# MKV58_1.net
KiCad netlist of a schematic drawn in Altium Designer
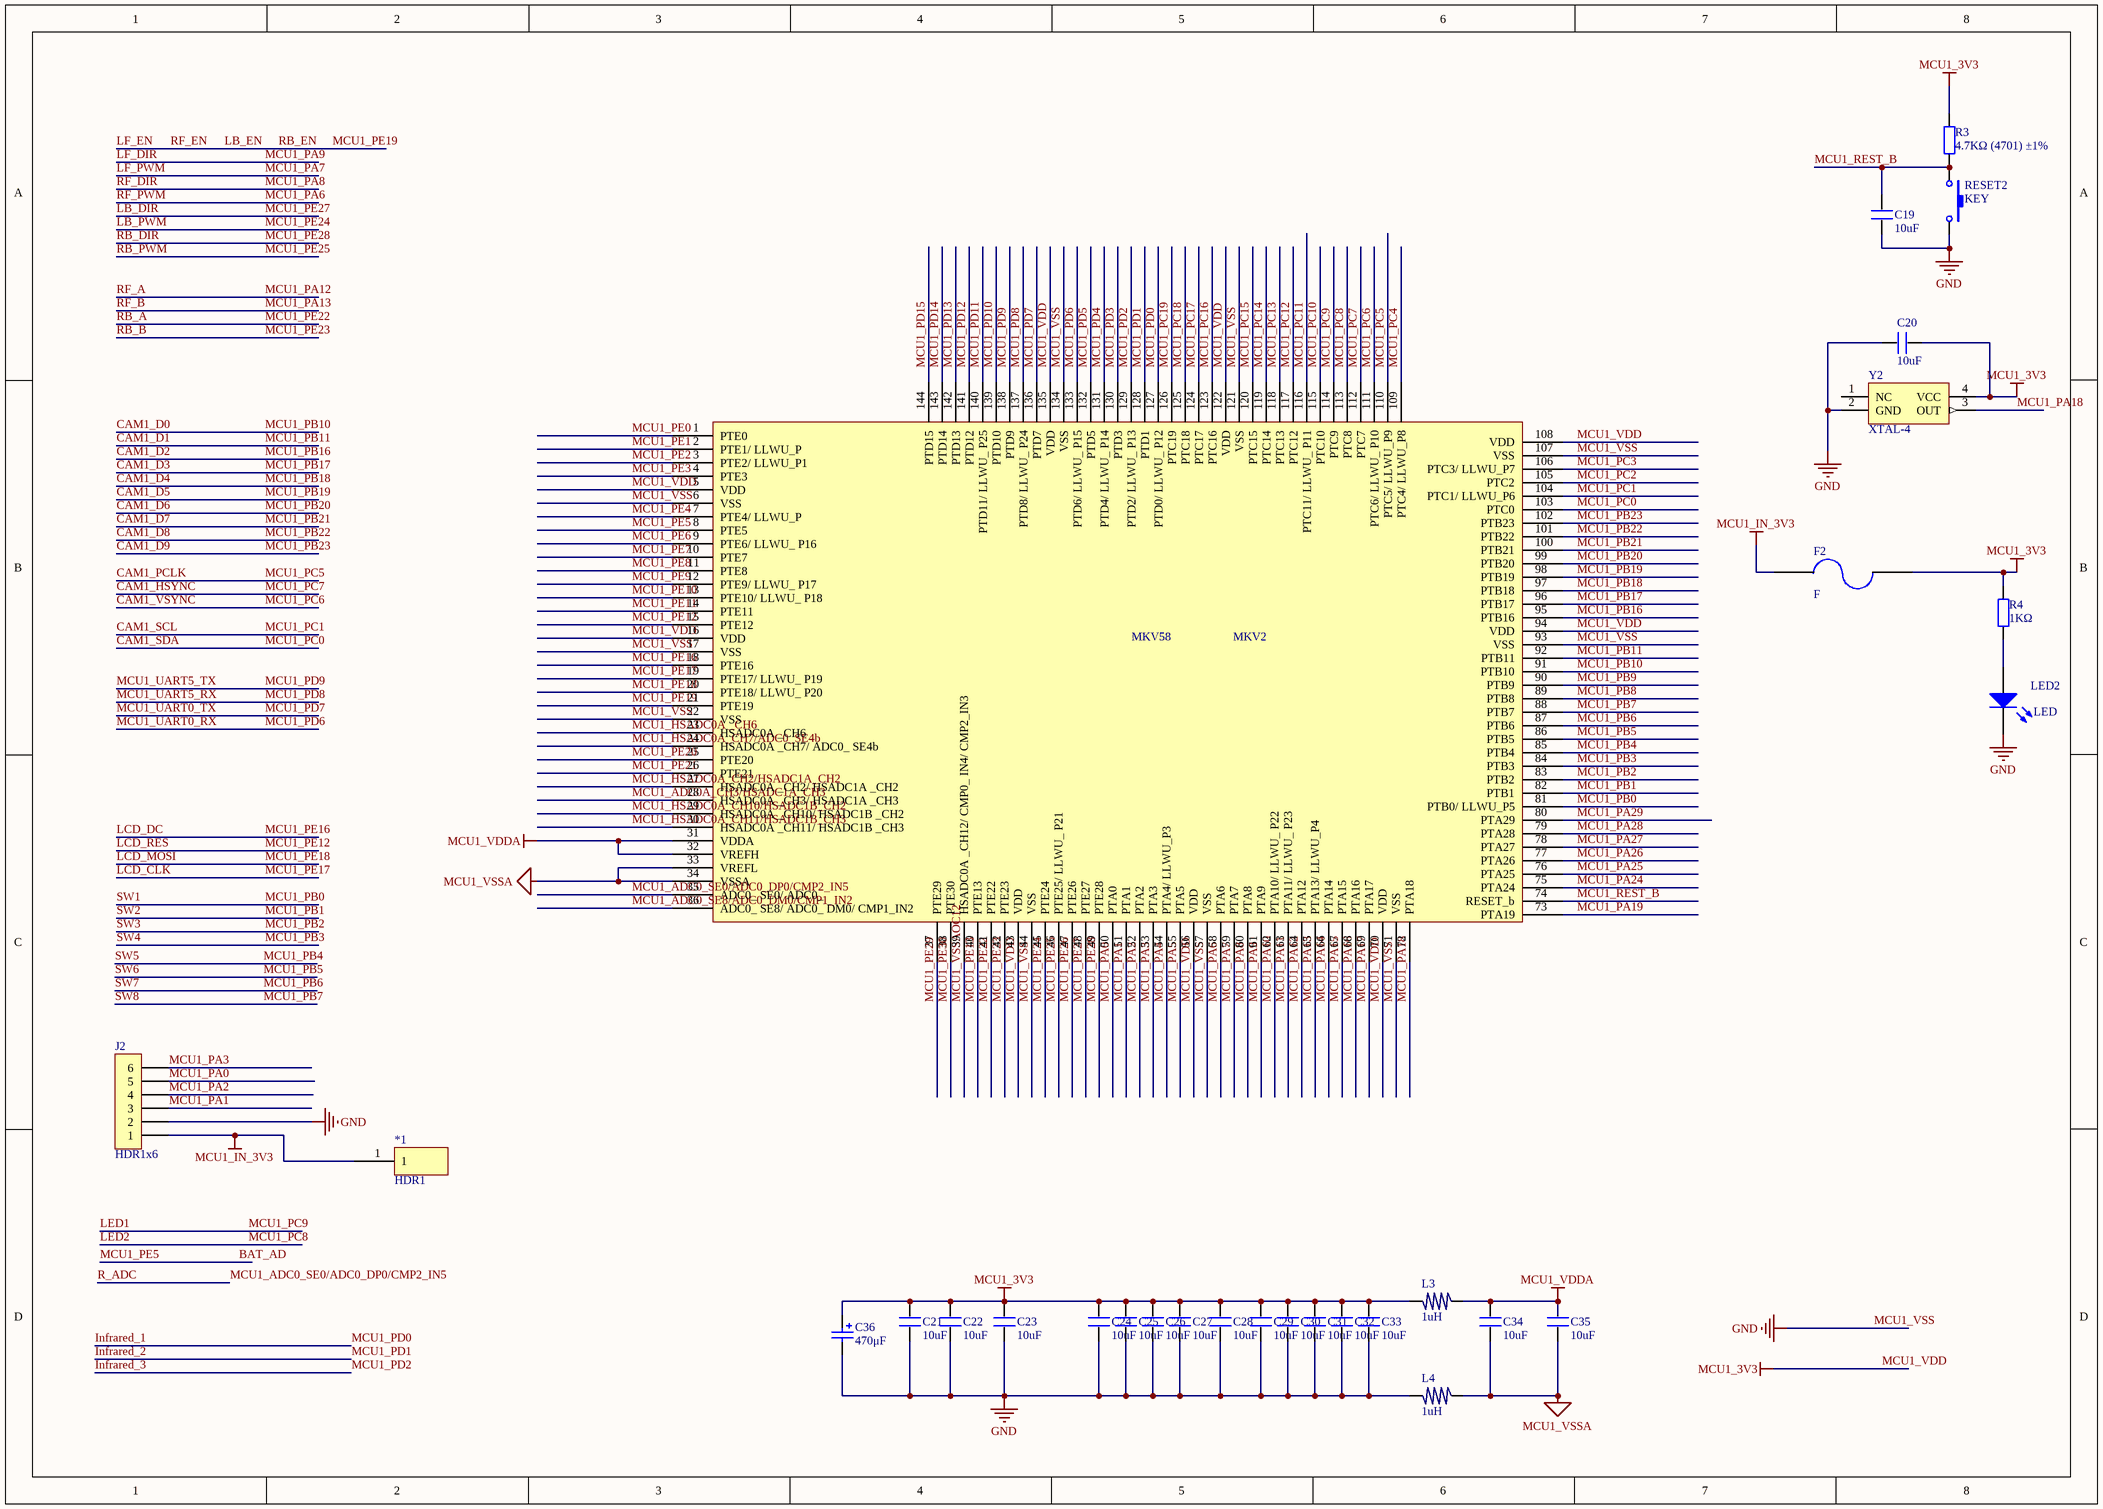
[diagram p0: MKV58(1.SchDoc]

(export (version "E")
  (design (tool "Eeschema 10.0.6"))
  (components
    (comp (ref "*1") (value "HDR1") (footprint "HDR1") (libsource (lib "MyLib") (part "HDR1")))
    (comp (ref "C19") (value "10uF") (footprint "0805_C") (libsource (lib "MyLib") (part "C")))
    (comp (ref "C20") (value "10uF") (footprint "0805_C") (libsource (lib "MyLib") (part "C")))
    (comp (ref "C21") (value "10uF") (footprint "0805_C") (libsource (lib "MyLib") (part "C")))
    (comp (ref "C22") (value "10uF") (footprint "0805_C") (libsource (lib "MyLib") (part "C")))
    (comp (ref "C23") (value "10uF") (footprint "0805_C") (libsource (lib "MyLib") (part "C")))
    (comp (ref "C24") (value "10uF") (footprint "0805_C") (libsource (lib "MyLib") (part "C")))
    (comp (ref "C25") (value "10uF") (footprint "0805_C") (libsource (lib "MyLib") (part "C")))
    (comp (ref "C26") (value "10uF") (footprint "0805_C") (libsource (lib "MyLib") (part "C")))
    (comp (ref "C27") (value "10uF") (footprint "0805_C") (libsource (lib "MyLib") (part "C")))
    (comp (ref "C28") (value "10uF") (footprint "0805_C") (libsource (lib "MyLib") (part "C")))
    (comp (ref "C29") (value "10uF") (footprint "0805_C") (libsource (lib "MyLib") (part "C")))
    (comp (ref "C30") (value "10uF") (footprint "0805_C") (libsource (lib "MyLib") (part "C")))
    (comp (ref "C31") (value "10uF") (footprint "0805_C") (libsource (lib "MyLib") (part "C")))
    (comp (ref "C32") (value "10uF") (footprint "0805_C") (libsource (lib "MyLib") (part "C")))
    (comp (ref "C33") (value "10uF") (footprint "0805_C") (libsource (lib "MyLib") (part "C")))
    (comp (ref "C34") (value "10uF") (footprint "0805_C") (libsource (lib "MyLib") (part "C")))
    (comp (ref "C35") (value "10uF") (footprint "0805_C") (libsource (lib "MyLib") (part "C")))
    (comp (ref "C36")
      (value "470μF")
      (footprint "CASE C6032")
      (fields (field (name "ALTIUM_UNNAMED_1") "470μF"))
      (libsource (lib "MyLib") (part "Cap(Ta)"))
    )
    (comp (ref "F2") (value "F") (footprint "0805_R") (libsource (lib "MKV58") (part "F")))
    (comp (ref "J2")
      (value "HDR1x6")
      (footprint "PIN-6-2.54-1.0")
      (description "Connector")
      (libsource (lib "MyLib") (part "HDR1x6"))
    )
    (comp (ref "L3") (value "1uH") (footprint "0805") (libsource (lib "MyLib") (part "L")))
    (comp (ref "L4") (value "1uH") (footprint "0805") (libsource (lib "MyLib") (part "L")))
    (comp (ref "LED2") (value "LED") (footprint "LED(0805)") (libsource (lib "MyLib") (part "LED(0805)")))
    (comp (ref "MKV2") (value "MKV58") (footprint "LQFP144") (libsource (lib "MyLib") (part "MKV58")))
    (comp (ref "R3")
      (value "4.7KΩ (4701) ±1%")
      (footprint "0805_R")
      (description "贴片电阻")
      (libsource (lib "MyLib") (part "0805 4.7KΩ (4701) 1%"))
    )
    (comp (ref "R4")
      (value "1KΩ")
      (footprint "0805_R")
      (description "贴片电阻")
      (libsource (lib "MyLib") (part "0805 1.5KΩ (1501) 1%"))
    )
    (comp (ref "RESET2") (value "KEY") (footprint "Key_PB") (libsource (lib "MyLib") (part "Key_1")))
    (comp (ref "Y2")
      (value "XTAL-4")
      (footprint "XTAL-5.0X3.2")
      (description "Oscillator")
      (libsource (lib "MyLib") (part "XTAL-4"))
    )
  )
  (nets
    (net (code "2") (name "/BAT_AD") (class "Default")
      (node (ref "MKV2") (pin "8") (pinfunction "PTE5_8") (pintype "passive"))
    )
    (net (code "3") (name "/CAM1_D0") (class "Default")
      (node (ref "MKV2") (pin "91") (pinfunction "PTB10_91") (pintype "passive"))
    )
    (net (code "4") (name "/CAM1_D1") (class "Default")
      (node (ref "MKV2") (pin "92") (pinfunction "PTB11_92") (pintype "passive"))
    )
    (net (code "5") (name "/CAM1_D2") (class "Default")
      (node (ref "MKV2") (pin "95") (pinfunction "PTB16_95") (pintype "passive"))
    )
    (net (code "6") (name "/CAM1_D3") (class "Default")
      (node (ref "MKV2") (pin "96") (pinfunction "PTB17_96") (pintype "passive"))
    )
    (net (code "7") (name "/CAM1_D4") (class "Default")
      (node (ref "MKV2") (pin "97") (pinfunction "PTB18_97") (pintype "passive"))
    )
    (net (code "8") (name "/CAM1_D5") (class "Default")
      (node (ref "MKV2") (pin "98") (pinfunction "PTB19_98") (pintype "passive"))
    )
    (net (code "9") (name "/CAM1_D6") (class "Default")
      (node (ref "MKV2") (pin "99") (pinfunction "PTB20_99") (pintype "passive"))
    )
    (net (code "10") (name "/CAM1_D7") (class "Default")
      (node (ref "MKV2") (pin "100") (pinfunction "PTB21_100") (pintype "passive"))
    )
    (net (code "11") (name "/CAM1_D8") (class "Default")
      (node (ref "MKV2") (pin "101") (pinfunction "PTB22_101") (pintype "passive"))
    )
    (net (code "12") (name "/CAM1_D9") (class "Default")
      (node (ref "MKV2") (pin "102") (pinfunction "PTB23_102") (pintype "passive"))
    )
    (net (code "13") (name "/CAM1_HSYNC") (class "Default")
      (node (ref "MKV2") (pin "112") (pinfunction "PTC7_112") (pintype "passive"))
    )
    (net (code "14") (name "/CAM1_PCLK") (class "Default")
      (node (ref "MKV2") (pin "110") (pinfunction "PTC5/_LLWU_P9_110") (pintype "passive"))
    )
    (net (code "15") (name "/CAM1_SCL") (class "Default")
      (node (ref "MKV2") (pin "104") (pinfunction "PTC1/_LLWU_P6_104") (pintype "passive"))
    )
    (net (code "16") (name "/CAM1_SDA") (class "Default")
      (node (ref "MKV2") (pin "103") (pinfunction "PTC0_103") (pintype "passive"))
    )
    (net (code "17") (name "/CAM1_VSYNC") (class "Default")
      (node (ref "MKV2") (pin "111") (pinfunction "PTC6/_LLWU__P10_111") (pintype "passive"))
    )
    (net (code "18") (name "/Infrared_1") (class "Default")
      (node (ref "MKV2") (pin "127") (pinfunction "PTD0/_LLWU__P12_127") (pintype "passive"))
    )
    (net (code "19") (name "/Infrared_2") (class "Default")
      (node (ref "MKV2") (pin "128") (pinfunction "PTD1_128") (pintype "passive"))
    )
    (net (code "20") (name "/Infrared_3") (class "Default")
      (node (ref "MKV2") (pin "129") (pinfunction "PTD2/_LLWU__P13_129") (pintype "passive"))
    )
    (net (code "21") (name "/LB_DIR") (class "Default")
      (node (ref "MKV2") (pin "48") (pinfunction "PTE27_48") (pintype "passive"))
    )
    (net (code "22") (name "/LB_EN") (class "Default")
      (node (ref "MKV2") (pin "21") (pinfunction "PTE19_21") (pintype "passive"))
    )
    (net (code "23") (name "/LB_PWM") (class "Default")
      (node (ref "MKV2") (pin "45") (pinfunction "PTE24_45") (pintype "passive"))
    )
    (net (code "24") (name "/LCD_CLK") (class "Default")
      (node (ref "MKV2") (pin "19") (pinfunction "PTE17/_LLWU__P19_19") (pintype "passive"))
    )
    (net (code "25") (name "/LCD_DC") (class "Default")
      (node (ref "MKV2") (pin "18") (pinfunction "PTE16_18") (pintype "passive"))
    )
    (net (code "26") (name "/LCD_MOSI") (class "Default")
      (node (ref "MKV2") (pin "20") (pinfunction "PTE18/_LLWU__P20_20") (pintype "passive"))
    )
    (net (code "27") (name "/LCD_RES") (class "Default")
      (node (ref "MKV2") (pin "15") (pinfunction "PTE12_15") (pintype "passive"))
    )
    (net (code "28") (name "/LED1") (class "Default")
      (node (ref "MKV2") (pin "114") (pinfunction "PTC9_114") (pintype "passive"))
    )
    (net (code "29") (name "/LED2") (class "Default")
      (node (ref "MKV2") (pin "113") (pinfunction "PTC8_113") (pintype "passive"))
    )
    (net (code "30") (name "/LF_DIR") (class "Default")
      (node (ref "MKV2") (pin "61") (pinfunction "PTA9_61") (pintype "passive"))
    )
    (net (code "31") (name "/LF_PWM") (class "Default")
      (node (ref "MKV2") (pin "59") (pinfunction "PTA7_59") (pintype "passive"))
    )
    (net (code "32") (name "/MCU1_ADC0A_CH3{slash}HSADC1A_CH3") (class "Default")
      (node (ref "MKV2") (pin "28") (pinfunction "HSADC0A__CH3/_HSADC1A__CH3_28") (pintype "passive"))
    )
    (net (code "33") (name "/MCU1_ADC0_SE0{slash}ADC0_DP0{slash}CMP2_IN5") (class "Default")
      (node (ref "MKV2") (pin "35") (pinfunction "ADC0__SE0/_ADC0__35") (pintype "passive"))
    )
    (net (code "34") (name "/MCU1_ADC0_SE8{slash}ADC0_DM0{slash}CMP1_IN2") (class "Default")
      (node (ref "MKV2") (pin "36") (pinfunction "ADC0__SE8/_ADC0__DM0/_CMP1_IN2_36") (pintype "passive"))
    )
    (net (code "35") (name "/MCU1_HSADC0A _CH6") (class "Default")
      (node (ref "MKV2") (pin "23") (pinfunction "HSADC0A__CH6_23") (pintype "passive"))
    )
    (net (code "36") (name "/MCU1_HSADC0A_CH2{slash}HSADC1A_CH2") (class "Default")
      (node (ref "MKV2") (pin "27") (pinfunction "HSADC0A__CH2/_HSADC1A__CH2_27") (pintype "passive"))
    )
    (net (code "37") (name "/MCU1_HSADC0A_CH7{slash}ADC0_SE4b") (class "Default")
      (node (ref "MKV2") (pin "24") (pinfunction "HSADC0A__CH7/_ADC0__SE4b_24") (pintype "passive"))
    )
    (net (code "38") (name "/MCU1_HSADC0A_CH10{slash}HSADC1B_CH2") (class "Default")
      (node (ref "MKV2") (pin "29") (pinfunction "HSADC0A__CH10/_HSADC1B__CH2_29") (pintype "passive"))
    )
    (net (code "39") (name "/MCU1_HSADC0A_CH11{slash}HSADC1B_CH3") (class "Default")
      (node (ref "MKV2") (pin "30") (pinfunction "HSADC0A__CH11/_HSADC1B__CH3_30") (pintype "passive"))
    )
    (net (code "40") (name "/MCU1_PA0") (class "Default")
      (node (ref "J2") (pin "5") (pinfunction "5_5") (pintype "passive"))
      (node (ref "MKV2") (pin "50") (pinfunction "PTA0_50") (pintype "passive"))
    )
    (net (code "41") (name "/MCU1_PA1") (class "Default")
      (node (ref "J2") (pin "3") (pinfunction "3_3") (pintype "passive"))
      (node (ref "MKV2") (pin "51") (pinfunction "PTA1_51") (pintype "passive"))
    )
    (net (code "42") (name "/MCU1_PA2") (class "Default")
      (node (ref "J2") (pin "4") (pinfunction "4_4") (pintype "passive"))
      (node (ref "MKV2") (pin "52") (pinfunction "PTA2_52") (pintype "passive"))
    )
    (net (code "43") (name "/MCU1_PA3") (class "Default")
      (node (ref "J2") (pin "6") (pinfunction "6_6") (pintype "passive"))
      (node (ref "MKV2") (pin "53") (pinfunction "PTA3_53") (pintype "passive"))
    )
    (net (code "44") (name "/MCU1_PA4") (class "Default")
      (node (ref "MKV2") (pin "54") (pinfunction "PTA4/_LLWU_P3_54") (pintype "passive"))
    )
    (net (code "45") (name "/MCU1_PA5") (class "Default")
      (node (ref "MKV2") (pin "55") (pinfunction "PTA5_55") (pintype "passive"))
    )
    (net (code "46") (name "/MCU1_PA6") (class "Default")
      (node (ref "MKV2") (pin "58") (pinfunction "PTA6_58") (pintype "passive"))
    )
    (net (code "47") (name "/MCU1_PA8") (class "Default")
      (node (ref "MKV2") (pin "60") (pinfunction "PTA8_60") (pintype "passive"))
    )
    (net (code "48") (name "/MCU1_PA10") (class "Default")
      (node (ref "MKV2") (pin "62") (pinfunction "PTA10/_LLWU__P22_62") (pintype "passive"))
    )
    (net (code "49") (name "/MCU1_PA11") (class "Default")
      (node (ref "MKV2") (pin "63") (pinfunction "PTA11/_LLWU__P23_63") (pintype "passive"))
    )
    (net (code "50") (name "/MCU1_PA12") (class "Default")
      (node (ref "MKV2") (pin "64") (pinfunction "PTA12_64") (pintype "passive"))
    )
    (net (code "51") (name "/MCU1_PA13") (class "Default")
      (node (ref "MKV2") (pin "65") (pinfunction "PTA13/_LLWU_P4_65") (pintype "passive"))
    )
    (net (code "52") (name "/MCU1_PA14") (class "Default")
      (node (ref "MKV2") (pin "66") (pinfunction "PTA14_66") (pintype "passive"))
    )
    (net (code "53") (name "/MCU1_PA15") (class "Default")
      (node (ref "MKV2") (pin "67") (pinfunction "PTA15_67") (pintype "passive"))
    )
    (net (code "54") (name "/MCU1_PA16") (class "Default")
      (node (ref "MKV2") (pin "68") (pinfunction "PTA16_68") (pintype "passive"))
    )
    (net (code "55") (name "/MCU1_PA17") (class "Default")
      (node (ref "MKV2") (pin "69") (pinfunction "PTA17_69") (pintype "passive"))
    )
    (net (code "56") (name "/MCU1_PA18") (class "Default")
      (node (ref "MKV2") (pin "72") (pinfunction "PTA18_72") (pintype "passive"))
      (node (ref "Y2") (pin "3") (pinfunction "OUT_3") (pintype "output"))
    )
    (net (code "57") (name "/MCU1_PA19") (class "Default")
      (node (ref "MKV2") (pin "73") (pinfunction "PTA19_73") (pintype "passive"))
    )
    (net (code "58") (name "/MCU1_PA24") (class "Default")
      (node (ref "MKV2") (pin "75") (pinfunction "PTA24_75") (pintype "passive"))
    )
    (net (code "59") (name "/MCU1_PA25") (class "Default")
      (node (ref "MKV2") (pin "76") (pinfunction "PTA25_76") (pintype "passive"))
    )
    (net (code "60") (name "/MCU1_PA26") (class "Default")
      (node (ref "MKV2") (pin "77") (pinfunction "PTA26_77") (pintype "passive"))
    )
    (net (code "61") (name "/MCU1_PA27") (class "Default")
      (node (ref "MKV2") (pin "78") (pinfunction "PTA27_78") (pintype "passive"))
    )
    (net (code "62") (name "/MCU1_PA28") (class "Default")
      (node (ref "MKV2") (pin "79") (pinfunction "PTA28_79") (pintype "passive"))
    )
    (net (code "63") (name "/MCU1_PA29") (class "Default")
      (node (ref "MKV2") (pin "80") (pinfunction "PTA29_80") (pintype "passive"))
    )
    (net (code "64") (name "/MCU1_PB0") (class "Default")
      (node (ref "MKV2") (pin "81") (pinfunction "PTB0/_LLWU_P5_81") (pintype "passive"))
    )
    (net (code "65") (name "/MCU1_PB1") (class "Default")
      (node (ref "MKV2") (pin "82") (pinfunction "PTB1_82") (pintype "passive"))
    )
    (net (code "66") (name "/MCU1_PB2") (class "Default")
      (node (ref "MKV2") (pin "83") (pinfunction "PTB2_83") (pintype "passive"))
    )
    (net (code "67") (name "/MCU1_PB3") (class "Default")
      (node (ref "MKV2") (pin "84") (pinfunction "PTB3_84") (pintype "passive"))
    )
    (net (code "68") (name "/MCU1_PB4") (class "Default")
      (node (ref "MKV2") (pin "85") (pinfunction "PTB4_85") (pintype "passive"))
    )
    (net (code "69") (name "/MCU1_PB5") (class "Default")
      (node (ref "MKV2") (pin "86") (pinfunction "PTB5_86") (pintype "passive"))
    )
    (net (code "70") (name "/MCU1_PB6") (class "Default")
      (node (ref "MKV2") (pin "87") (pinfunction "PTB6_87") (pintype "passive"))
    )
    (net (code "71") (name "/MCU1_PB7") (class "Default")
      (node (ref "MKV2") (pin "88") (pinfunction "PTB7_88") (pintype "passive"))
    )
    (net (code "72") (name "/MCU1_PB8") (class "Default")
      (node (ref "MKV2") (pin "89") (pinfunction "PTB8_89") (pintype "passive"))
    )
    (net (code "73") (name "/MCU1_PB9") (class "Default")
      (node (ref "MKV2") (pin "90") (pinfunction "PTB9_90") (pintype "passive"))
    )
    (net (code "74") (name "/MCU1_PC2") (class "Default")
      (node (ref "MKV2") (pin "105") (pinfunction "PTC2_105") (pintype "passive"))
    )
    (net (code "75") (name "/MCU1_PC3") (class "Default")
      (node (ref "MKV2") (pin "106") (pinfunction "PTC3/_LLWU_P7_106") (pintype "passive"))
    )
    (net (code "76") (name "/MCU1_PC4") (class "Default")
      (node (ref "MKV2") (pin "109") (pinfunction "PTC4/_LLWU_P8_109") (pintype "passive"))
    )
    (net (code "77") (name "/MCU1_PC10") (class "Default")
      (node (ref "MKV2") (pin "115") (pinfunction "PTC10_115") (pintype "passive"))
    )
    (net (code "78") (name "/MCU1_PC11") (class "Default")
      (node (ref "MKV2") (pin "116") (pinfunction "PTC11/_LLWU__P11_116") (pintype "passive"))
    )
    (net (code "79") (name "/MCU1_PC12") (class "Default")
      (node (ref "MKV2") (pin "117") (pinfunction "PTC12_117") (pintype "passive"))
    )
    (net (code "80") (name "/MCU1_PC13") (class "Default")
      (node (ref "MKV2") (pin "118") (pinfunction "PTC13_118") (pintype "passive"))
    )
    (net (code "81") (name "/MCU1_PC14") (class "Default")
      (node (ref "MKV2") (pin "119") (pinfunction "PTC14_119") (pintype "passive"))
    )
    (net (code "82") (name "/MCU1_PC15") (class "Default")
      (node (ref "MKV2") (pin "120") (pinfunction "PTC15_120") (pintype "passive"))
    )
    (net (code "83") (name "/MCU1_PC16") (class "Default")
      (node (ref "MKV2") (pin "123") (pinfunction "PTC16_123") (pintype "passive"))
    )
    (net (code "84") (name "/MCU1_PC17") (class "Default")
      (node (ref "MKV2") (pin "124") (pinfunction "PTC17_124") (pintype "passive"))
    )
    (net (code "85") (name "/MCU1_PC18") (class "Default")
      (node (ref "MKV2") (pin "125") (pinfunction "PTC18_125") (pintype "passive"))
    )
    (net (code "86") (name "/MCU1_PC19") (class "Default")
      (node (ref "MKV2") (pin "126") (pinfunction "PTC19_126") (pintype "passive"))
    )
    (net (code "87") (name "/MCU1_PD3") (class "Default")
      (node (ref "MKV2") (pin "130") (pinfunction "PTD3_130") (pintype "passive"))
    )
    (net (code "88") (name "/MCU1_PD4") (class "Default")
      (node (ref "MKV2") (pin "131") (pinfunction "PTD4/_LLWU__P14_131") (pintype "passive"))
    )
    (net (code "89") (name "/MCU1_PD5") (class "Default")
      (node (ref "MKV2") (pin "132") (pinfunction "PTD5_132") (pintype "passive"))
    )
    (net (code "90") (name "/MCU1_PD6") (class "Default")
      (node (ref "MKV2") (pin "133") (pinfunction "PTD6/_LLWU__P15_133") (pintype "passive"))
    )
    (net (code "91") (name "/MCU1_PD7") (class "Default")
      (node (ref "MKV2") (pin "136") (pinfunction "PTD7_136") (pintype "passive"))
    )
    (net (code "92") (name "/MCU1_PD8") (class "Default")
      (node (ref "MKV2") (pin "137") (pinfunction "PTD8/_LLWU__P24_137") (pintype "passive"))
    )
    (net (code "93") (name "/MCU1_PD9") (class "Default")
      (node (ref "MKV2") (pin "138") (pinfunction "PTD9_138") (pintype "passive"))
    )
    (net (code "94") (name "/MCU1_PD10") (class "Default")
      (node (ref "MKV2") (pin "139") (pinfunction "PTD10_139") (pintype "passive"))
    )
    (net (code "95") (name "/MCU1_PD11") (class "Default")
      (node (ref "MKV2") (pin "140") (pinfunction "PTD11/_LLWU__P25_140") (pintype "passive"))
    )
    (net (code "96") (name "/MCU1_PD12") (class "Default")
      (node (ref "MKV2") (pin "141") (pinfunction "PTD12_141") (pintype "passive"))
    )
    (net (code "97") (name "/MCU1_PD13") (class "Default")
      (node (ref "MKV2") (pin "142") (pinfunction "PTD13_142") (pintype "passive"))
    )
    (net (code "98") (name "/MCU1_PD14") (class "Default")
      (node (ref "MKV2") (pin "143") (pinfunction "PTD14_143") (pintype "passive"))
    )
    (net (code "99") (name "/MCU1_PD15") (class "Default")
      (node (ref "MKV2") (pin "144") (pinfunction "PTD15_144") (pintype "passive"))
    )
    (net (code "100") (name "/MCU1_PE0") (class "Default")
      (node (ref "MKV2") (pin "1") (pinfunction "PTE0_1") (pintype "passive"))
    )
    (net (code "101") (name "/MCU1_PE1") (class "Default")
      (node (ref "MKV2") (pin "2") (pinfunction "PTE1/_LLWU_P_2") (pintype "passive"))
    )
    (net (code "102") (name "/MCU1_PE2") (class "Default")
      (node (ref "MKV2") (pin "3") (pinfunction "PTE2/_LLWU_P1_3") (pintype "passive"))
    )
    (net (code "103") (name "/MCU1_PE3") (class "Default")
      (node (ref "MKV2") (pin "4") (pinfunction "PTE3_4") (pintype "passive"))
    )
    (net (code "104") (name "/MCU1_PE4") (class "Default")
      (node (ref "MKV2") (pin "7") (pinfunction "PTE4/_LLWU_P_7") (pintype "passive"))
    )
    (net (code "105") (name "/MCU1_PE6") (class "Default")
      (node (ref "MKV2") (pin "9") (pinfunction "PTE6/_LLWU__P16_9") (pintype "passive"))
    )
    (net (code "106") (name "/MCU1_PE7") (class "Default")
      (node (ref "MKV2") (pin "10") (pinfunction "PTE7_10") (pintype "passive"))
    )
    (net (code "107") (name "/MCU1_PE8") (class "Default")
      (node (ref "MKV2") (pin "11") (pinfunction "PTE8_11") (pintype "passive"))
    )
    (net (code "108") (name "/MCU1_PE9") (class "Default")
      (node (ref "MKV2") (pin "12") (pinfunction "PTE9/_LLWU__P17_12") (pintype "passive"))
    )
    (net (code "109") (name "/MCU1_PE10") (class "Default")
      (node (ref "MKV2") (pin "13") (pinfunction "PTE10/_LLWU__P18_13") (pintype "passive"))
    )
    (net (code "110") (name "/MCU1_PE11") (class "Default")
      (node (ref "MKV2") (pin "14") (pinfunction "PTE11_14") (pintype "passive"))
    )
    (net (code "111") (name "/MCU1_PE13") (class "Default")
      (node (ref "MKV2") (pin "40") (pinfunction "PTE13_40") (pintype "passive"))
    )
    (net (code "112") (name "/MCU1_PE20") (class "Default")
      (node (ref "MKV2") (pin "25") (pinfunction "PTE20_25") (pintype "passive"))
    )
    (net (code "113") (name "/MCU1_PE21") (class "Default")
      (node (ref "MKV2") (pin "26") (pinfunction "PTE21_26") (pintype "passive"))
    )
    (net (code "114") (name "/MCU1_PE22") (class "Default")
      (node (ref "MKV2") (pin "41") (pinfunction "PTE22_41") (pintype "passive"))
    )
    (net (code "115") (name "/MCU1_PE23") (class "Default")
      (node (ref "MKV2") (pin "42") (pinfunction "PTE23_42") (pintype "passive"))
    )
    (net (code "116") (name "/MCU1_PE25") (class "Default")
      (node (ref "MKV2") (pin "46") (pinfunction "PTE25/_LLWU__P21_46") (pintype "passive"))
    )
    (net (code "117") (name "/MCU1_PE26") (class "Default")
      (node (ref "MKV2") (pin "47") (pinfunction "PTE26_47") (pintype "passive"))
    )
    (net (code "118") (name "/MCU1_PE28") (class "Default")
      (node (ref "MKV2") (pin "49") (pinfunction "PTE28_49") (pintype "passive"))
    )
    (net (code "119") (name "/MCU1_PE29") (class "Default")
      (node (ref "MKV2") (pin "37") (pinfunction "PTE29_37") (pintype "passive"))
    )
    (net (code "120") (name "/MCU1_PE30") (class "Default")
      (node (ref "MKV2") (pin "38") (pinfunction "PTE30_38") (pintype "passive"))
    )
    (net (code "121") (name "/MCU1_REST_B") (class "Default")
      (node (ref "C19") (pin "2") (pintype "passive"))
      (node (ref "MKV2") (pin "74") (pinfunction "RESET_b_74") (pintype "passive"))
      (node (ref "R3") (pin "1") (pinfunction "1_1") (pintype "passive"))
      (node (ref "RESET2") (pin "1") (pinfunction "1_1") (pintype "passive"))
    )
    (net (code "122") (name "/MCU1_VSSAOC12") (class "Default")
      (node (ref "MKV2") (pin "39") (pinfunction "HSADC0A__CH12/_CMP0__IN4/_CMP2_IN3_39") (pintype "passive"))
    )
    (net (code "123") (name "GND") (class "Default")
      (node (ref "C19") (pin "1") (pintype "passive"))
      (node (ref "C20") (pin "1") (pintype "passive"))
      (node (ref "C21") (pin "1") (pintype "passive"))
      (node (ref "C22") (pin "1") (pintype "passive"))
      (node (ref "C23") (pin "1") (pintype "passive"))
      (node (ref "C24") (pin "1") (pintype "passive"))
      (node (ref "C25") (pin "1") (pintype "passive"))
      (node (ref "C26") (pin "1") (pintype "passive"))
      (node (ref "C27") (pin "1") (pintype "passive"))
      (node (ref "C28") (pin "1") (pintype "passive"))
      (node (ref "C29") (pin "1") (pintype "passive"))
      (node (ref "C30") (pin "1") (pintype "passive"))
      (node (ref "C31") (pin "1") (pintype "passive"))
      (node (ref "C32") (pin "1") (pintype "passive"))
      (node (ref "C33") (pin "1") (pintype "passive"))
      (node (ref "C36") (pin "2") (pinfunction "2_2") (pintype "passive"))
      (node (ref "J2") (pin "2") (pinfunction "2_2") (pintype "passive"))
      (node (ref "L4") (pin "2") (pintype "passive"))
      (node (ref "LED2") (pin "2") (pinfunction "K_2") (pintype "passive"))
      (node (ref "MKV2") (pin "107") (pinfunction "VSS_107") (pintype "passive"))
      (node (ref "MKV2") (pin "121") (pinfunction "VSS_121") (pintype "passive"))
      (node (ref "MKV2") (pin "134") (pinfunction "VSS_134") (pintype "passive"))
      (node (ref "MKV2") (pin "17") (pinfunction "VSS_17") (pintype "passive"))
      (node (ref "MKV2") (pin "22") (pinfunction "VSS_22") (pintype "passive"))
      (node (ref "MKV2") (pin "44") (pinfunction "VSS_44") (pintype "passive"))
      (node (ref "MKV2") (pin "57") (pinfunction "VSS_57") (pintype "passive"))
      (node (ref "MKV2") (pin "6") (pinfunction "VSS_6") (pintype "passive"))
      (node (ref "MKV2") (pin "71") (pinfunction "VSS_71") (pintype "passive"))
      (node (ref "MKV2") (pin "93") (pinfunction "VSS_93") (pintype "passive"))
      (node (ref "RESET2") (pin "2") (pinfunction "2_2") (pintype "passive"))
      (node (ref "Y2") (pin "2") (pinfunction "GND_2") (pintype "power_in"))
    )
    (net (code "124") (name "MCU1_3V3") (class "Default")
      (node (ref "C20") (pin "2") (pintype "passive"))
      (node (ref "C21") (pin "2") (pintype "passive"))
      (node (ref "C22") (pin "2") (pintype "passive"))
      (node (ref "C23") (pin "2") (pintype "passive"))
      (node (ref "C24") (pin "2") (pintype "passive"))
      (node (ref "C25") (pin "2") (pintype "passive"))
      (node (ref "C26") (pin "2") (pintype "passive"))
      (node (ref "C27") (pin "2") (pintype "passive"))
      (node (ref "C28") (pin "2") (pintype "passive"))
      (node (ref "C29") (pin "2") (pintype "passive"))
      (node (ref "C30") (pin "2") (pintype "passive"))
      (node (ref "C31") (pin "2") (pintype "passive"))
      (node (ref "C32") (pin "2") (pintype "passive"))
      (node (ref "C33") (pin "2") (pintype "passive"))
      (node (ref "C36") (pin "1") (pinfunction "1_1") (pintype "passive"))
      (node (ref "F2") (pin "2") (pinfunction "1_2") (pintype "passive"))
      (node (ref "L3") (pin "2") (pintype "passive"))
      (node (ref "MKV2") (pin "108") (pinfunction "VDD_108") (pintype "passive"))
      (node (ref "MKV2") (pin "122") (pinfunction "VDD_122") (pintype "passive"))
      (node (ref "MKV2") (pin "135") (pinfunction "VDD_135") (pintype "passive"))
      (node (ref "MKV2") (pin "16") (pinfunction "VDD_16") (pintype "passive"))
      (node (ref "MKV2") (pin "43") (pinfunction "VDD_43") (pintype "passive"))
      (node (ref "MKV2") (pin "5") (pinfunction "VDD_5") (pintype "passive"))
      (node (ref "MKV2") (pin "56") (pinfunction "VDD_56") (pintype "passive"))
      (node (ref "MKV2") (pin "70") (pinfunction "VDD_70") (pintype "passive"))
      (node (ref "MKV2") (pin "94") (pinfunction "VDD_94") (pintype "passive"))
      (node (ref "R3") (pin "2") (pinfunction "2_2") (pintype "passive"))
      (node (ref "R4") (pin "2") (pinfunction "2_2") (pintype "passive"))
      (node (ref "Y2") (pin "4") (pinfunction "VCC_4") (pintype "power_in"))
    )
    (net (code "125") (name "MCU1_IN_3V3") (class "Default")
      (node (ref "*1") (pin "1") (pinfunction "1_1") (pintype "passive"))
      (node (ref "F2") (pin "1") (pinfunction "0_1") (pintype "passive"))
      (node (ref "J2") (pin "1") (pinfunction "1_1") (pintype "passive"))
    )
    (net (code "126") (name "MCU1_VDDA") (class "Default")
      (node (ref "C34") (pin "2") (pintype "passive"))
      (node (ref "C35") (pin "2") (pintype "passive"))
      (node (ref "L3") (pin "1") (pintype "passive"))
      (node (ref "MKV2") (pin "31") (pinfunction "VDDA_31") (pintype "passive"))
      (node (ref "MKV2") (pin "32") (pinfunction "VREFH_32") (pintype "passive"))
    )
    (net (code "127") (name "MCU1_VSSA") (class "Default")
      (node (ref "C34") (pin "1") (pintype "passive"))
      (node (ref "C35") (pin "1") (pintype "passive"))
      (node (ref "L4") (pin "1") (pintype "passive"))
      (node (ref "MKV2") (pin "33") (pinfunction "VREFL_33") (pintype "passive"))
      (node (ref "MKV2") (pin "34") (pinfunction "VSSA_34") (pintype "passive"))
    )
    (net (code "128") (name "Net-(LED2-A)") (class "Default")
      (node (ref "LED2") (pin "1") (pinfunction "A_1") (pintype "passive"))
      (node (ref "R4") (pin "1") (pinfunction "1_1") (pintype "passive"))
    )
    (net (code "129") (name "unconnected-(Y2-NC-Pad1)") (class "Default")
      (node (ref "Y2") (pin "1") (pinfunction "NC_1") (pintype "passive"))
    )
  )
)
